# MOSFET_Board.net
KiCad netlist of a schematic drawn in EAGLE
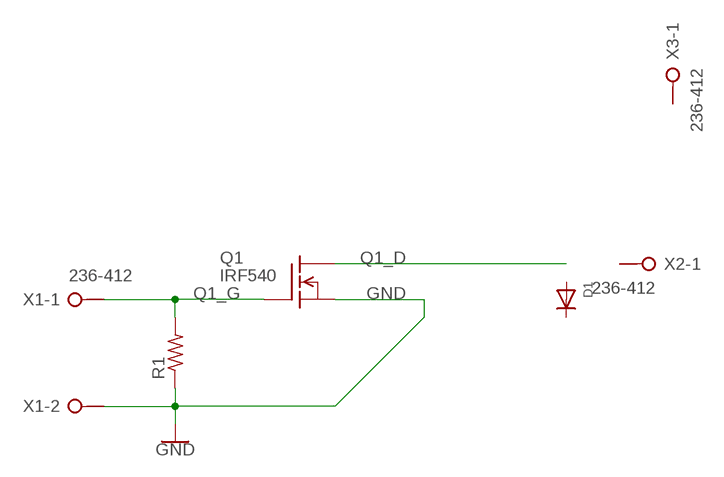
[diagram p0: schematic, sheet 1]

(export (version "E")
  (design (tool "Eeschema 10.0.6"))
  (components
    (comp (ref "D1")
      (value "DIODESMA")
      (footprint "eagle-import:SMADIODE")
      (libsource (lib "eagle-import") (part "DIODESMA"))
    )
    (comp (ref "Q1")
      (value "IRF540")
      (footprint "eagle-import:TO220")
      (libsource (lib "eagle-import") (part "IRF540"))
    )
    (comp (ref "R1")
      (value "R-US_0204/2V")
      (footprint "eagle-import:0204V")
      (libsource (lib "eagle-import") (part "R-US_0204/2V"))
    )
    (comp (ref "X1")
      (value "236-412")
      (footprint "eagle-import:236-412")
      (fields (field (name "MF") "Wago Corporation") (field (name "MPN") "0236-0412"))
      (libsource (lib "eagle-import") (part "236-412"))
    )
    (comp (ref "X2")
      (value "236-412")
      (footprint "eagle-import:236-412")
      (fields (field (name "MF") "Wago Corporation") (field (name "MPN") "0236-0412"))
      (libsource (lib "eagle-import") (part "236-412"))
    )
    (comp (ref "X3")
      (value "236-412")
      (footprint "eagle-import:236-412")
      (fields (field (name "MF") "Wago Corporation") (field (name "MPN") "0236-0412"))
      (libsource (lib "eagle-import") (part "236-412"))
    )
  )
  (nets
    (net (code "1") (name "/Q1_D") (class "Default")
      (node (ref "Q1") (pin "2") (pinfunction "D_2") (pintype "passive"))
    )
    (net (code "2") (name "/Q1_G") (class "Default")
      (node (ref "Q1") (pin "1") (pinfunction "G_1") (pintype "passive"))
      (node (ref "R1") (pin "2") (pinfunction "2_2") (pintype "passive"))
      (node (ref "X1") (pin "1@1") (pinfunction "KL1_1@1") (pintype "passive"))
    )
    (net (code "3") (name "GND") (class "Default")
      (node (ref "Q1") (pin "3") (pinfunction "S_3") (pintype "passive"))
      (node (ref "R1") (pin "1") (pinfunction "1_1") (pintype "passive"))
      (node (ref "X1") (pin "2@1") (pinfunction "KL1_2@1") (pintype "passive"))
    )
    (net (code "4") (name "unconnected-(D1-PadA)") (class "Default")
      (node (ref "D1") (pin "A") (pinfunction "A_A") (pintype "passive"))
    )
    (net (code "5") (name "unconnected-(D1-PadC)") (class "Default")
      (node (ref "D1") (pin "C") (pinfunction "C_C") (pintype "passive"))
    )
    (net (code "6") (name "unconnected-(X1A-KL2-Pad1@2)") (class "Default")
      (node (ref "X1") (pin "1@2") (pinfunction "KL2_1@2") (pintype "passive"))
    )
    (net (code "7") (name "unconnected-(X1E-KL2-Pad2@2)") (class "Default")
      (node (ref "X1") (pin "2@2") (pinfunction "KL2_2@2") (pintype "passive"))
    )
    (net (code "8") (name "unconnected-(X2A-KL1-Pad1@1)") (class "Default")
      (node (ref "X2") (pin "1@1") (pinfunction "KL1_1@1") (pintype "passive"))
    )
    (net (code "9") (name "unconnected-(X2A-KL2-Pad1@2)") (class "Default")
      (node (ref "X2") (pin "1@2") (pinfunction "KL2_1@2") (pintype "passive"))
    )
    (net (code "10") (name "unconnected-(X3A-KL1-Pad1@1)") (class "Default")
      (node (ref "X3") (pin "1@1") (pinfunction "KL1_1@1") (pintype "passive"))
    )
    (net (code "11") (name "unconnected-(X3A-KL2-Pad1@2)") (class "Default")
      (node (ref "X3") (pin "1@2") (pinfunction "KL2_1@2") (pintype "passive"))
    )
  )
)
